# arduino.net
KiCad netlist of a schematic drawn in EAGLE
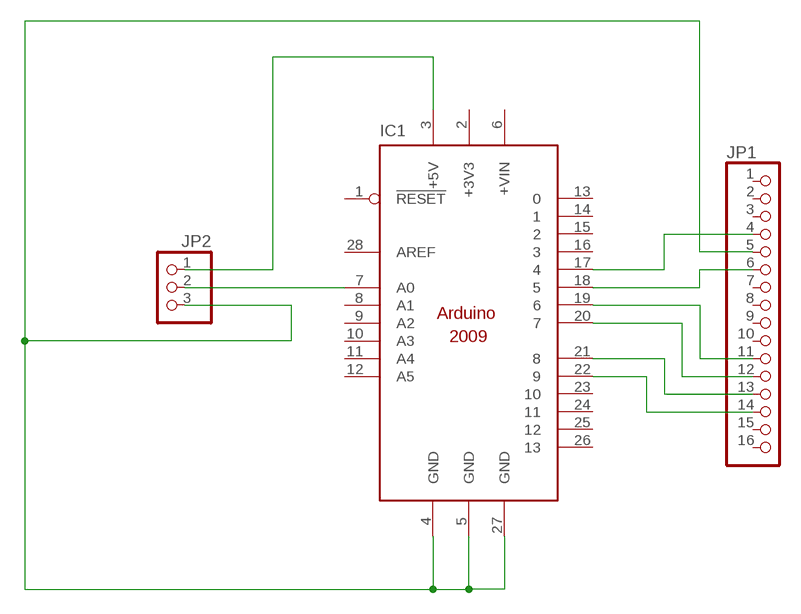
[diagram p0: schematic, sheet 1]

(export (version "E")
  (design (tool "Eeschema 10.0.6"))
  (components
    (comp (ref "IC1")
      (value "ARDUINO2009_12")
      (footprint "eagle-import:ARDUINO2009_2")
      (libsource (lib "eagle-import") (part "ARDUINO2009_12"))
    )
    (comp (ref "JP1")
      (value "PINHD-1X16")
      (footprint "eagle-import:1X16")
      (libsource (lib "eagle-import") (part "PINHD-1X16"))
    )
    (comp (ref "JP2")
      (value "PINHD-1X3")
      (footprint "eagle-import:1X03")
      (libsource (lib "eagle-import") (part "PINHD-1X3"))
    )
  )
  (nets
    (net (code "1") (name "/+3V3") (class "Default")
      (node (ref "IC1") (pin "2") (pinfunction "+3V3_2") (pintype "power_in"))
    )
    (net (code "2") (name "Net-(IC1-+5V)") (class "Default")
      (node (ref "IC1") (pin "3") (pinfunction "+5V_3") (pintype "power_in"))
      (node (ref "JP2") (pin "1") (pinfunction "1_1") (pintype "passive"))
    )
    (net (code "3") (name "Net-(IC1-4)") (class "Default")
      (node (ref "IC1") (pin "17") (pinfunction "4_17") (pintype "bidirectional"))
      (node (ref "JP1") (pin "4") (pinfunction "4_4") (pintype "passive"))
    )
    (net (code "4") (name "Net-(IC1-5)") (class "Default")
      (node (ref "IC1") (pin "18") (pinfunction "5_18") (pintype "bidirectional"))
      (node (ref "JP1") (pin "6") (pinfunction "6_6") (pintype "passive"))
    )
    (net (code "5") (name "Net-(IC1-6)") (class "Default")
      (node (ref "IC1") (pin "19") (pinfunction "6_19") (pintype "bidirectional"))
      (node (ref "JP1") (pin "11") (pinfunction "11_11") (pintype "passive"))
    )
    (net (code "6") (name "Net-(IC1-7)") (class "Default")
      (node (ref "IC1") (pin "20") (pinfunction "7_20") (pintype "bidirectional"))
      (node (ref "JP1") (pin "12") (pinfunction "12_12") (pintype "passive"))
    )
    (net (code "7") (name "Net-(IC1-8)") (class "Default")
      (node (ref "IC1") (pin "21") (pinfunction "8_21") (pintype "bidirectional"))
      (node (ref "JP1") (pin "13") (pinfunction "13_13") (pintype "passive"))
    )
    (net (code "8") (name "Net-(IC1-9)") (class "Default")
      (node (ref "IC1") (pin "22") (pinfunction "9_22") (pintype "bidirectional"))
      (node (ref "JP1") (pin "14") (pinfunction "14_14") (pintype "passive"))
    )
    (net (code "9") (name "Net-(IC1-A0)") (class "Default")
      (node (ref "IC1") (pin "7") (pinfunction "A0_7") (pintype "bidirectional"))
      (node (ref "JP2") (pin "2") (pinfunction "2_2") (pintype "passive"))
    )
    (net (code "10") (name "Net-(IC1-GND-Pad27)") (class "Default")
      (node (ref "IC1") (pin "27") (pinfunction "GND_27") (pintype "power_in"))
      (node (ref "IC1") (pin "4") (pinfunction "GND_4") (pintype "power_in"))
      (node (ref "IC1") (pin "5") (pinfunction "GND_5") (pintype "power_in"))
      (node (ref "JP1") (pin "5") (pinfunction "5_5") (pintype "passive"))
      (node (ref "JP2") (pin "3") (pinfunction "3_3") (pintype "passive"))
    )
    (net (code "11") (name "unconnected-(IC1-+VIN-Pad6)") (class "Default")
      (node (ref "IC1") (pin "6") (pinfunction "+VIN_6") (pintype "bidirectional"))
    )
    (net (code "12") (name "unconnected-(IC1-0-Pad13)") (class "Default")
      (node (ref "IC1") (pin "13") (pinfunction "0_13") (pintype "bidirectional"))
    )
    (net (code "13") (name "unconnected-(IC1-1-Pad14)") (class "Default")
      (node (ref "IC1") (pin "14") (pinfunction "1_14") (pintype "bidirectional"))
    )
    (net (code "14") (name "unconnected-(IC1-2-Pad15)") (class "Default")
      (node (ref "IC1") (pin "15") (pinfunction "2_15") (pintype "bidirectional"))
    )
    (net (code "15") (name "unconnected-(IC1-3-Pad16)") (class "Default")
      (node (ref "IC1") (pin "16") (pinfunction "3_16") (pintype "bidirectional"))
    )
    (net (code "16") (name "unconnected-(IC1-10-Pad23)") (class "Default")
      (node (ref "IC1") (pin "23") (pinfunction "10_23") (pintype "bidirectional"))
    )
    (net (code "17") (name "unconnected-(IC1-11-Pad24)") (class "Default")
      (node (ref "IC1") (pin "24") (pinfunction "11_24") (pintype "bidirectional"))
    )
    (net (code "18") (name "unconnected-(IC1-12-Pad25)") (class "Default")
      (node (ref "IC1") (pin "25") (pinfunction "12_25") (pintype "bidirectional"))
    )
    (net (code "19") (name "unconnected-(IC1-13-Pad26)") (class "Default")
      (node (ref "IC1") (pin "26") (pinfunction "13_26") (pintype "bidirectional"))
    )
    (net (code "20") (name "unconnected-(IC1-A1-Pad8)") (class "Default")
      (node (ref "IC1") (pin "8") (pinfunction "A1_8") (pintype "bidirectional"))
    )
    (net (code "21") (name "unconnected-(IC1-A2-Pad9)") (class "Default")
      (node (ref "IC1") (pin "9") (pinfunction "A2_9") (pintype "bidirectional"))
    )
    (net (code "22") (name "unconnected-(IC1-A3-Pad10)") (class "Default")
      (node (ref "IC1") (pin "10") (pinfunction "A3_10") (pintype "bidirectional"))
    )
    (net (code "23") (name "unconnected-(IC1-A4-Pad11)") (class "Default")
      (node (ref "IC1") (pin "11") (pinfunction "A4_11") (pintype "bidirectional"))
    )
    (net (code "24") (name "unconnected-(IC1-A5-Pad12)") (class "Default")
      (node (ref "IC1") (pin "12") (pinfunction "A5_12") (pintype "bidirectional"))
    )
    (net (code "25") (name "unconnected-(IC1-AREF-Pad28)") (class "Default")
      (node (ref "IC1") (pin "28") (pinfunction "AREF_28") (pintype "bidirectional"))
    )
    (net (code "26") (name "unconnected-(IC1-~{RESET}-Pad1)") (class "Default")
      (node (ref "IC1") (pin "1") (pinfunction "~{RESET}_1") (pintype "bidirectional"))
    )
    (net (code "27") (name "unconnected-(JP1-Pad1)") (class "Default")
      (node (ref "JP1") (pin "1") (pinfunction "1_1") (pintype "passive"))
    )
    (net (code "28") (name "unconnected-(JP1-Pad2)") (class "Default")
      (node (ref "JP1") (pin "2") (pinfunction "2_2") (pintype "passive"))
    )
    (net (code "29") (name "unconnected-(JP1-Pad3)") (class "Default")
      (node (ref "JP1") (pin "3") (pinfunction "3_3") (pintype "passive"))
    )
    (net (code "30") (name "unconnected-(JP1-Pad7)") (class "Default")
      (node (ref "JP1") (pin "7") (pinfunction "7_7") (pintype "passive"))
    )
    (net (code "31") (name "unconnected-(JP1-Pad8)") (class "Default")
      (node (ref "JP1") (pin "8") (pinfunction "8_8") (pintype "passive"))
    )
    (net (code "32") (name "unconnected-(JP1-Pad9)") (class "Default")
      (node (ref "JP1") (pin "9") (pinfunction "9_9") (pintype "passive"))
    )
    (net (code "33") (name "unconnected-(JP1-Pad10)") (class "Default")
      (node (ref "JP1") (pin "10") (pinfunction "10_10") (pintype "passive"))
    )
    (net (code "34") (name "unconnected-(JP1-Pad15)") (class "Default")
      (node (ref "JP1") (pin "15") (pinfunction "15_15") (pintype "passive"))
    )
    (net (code "35") (name "unconnected-(JP1-Pad16)") (class "Default")
      (node (ref "JP1") (pin "16") (pinfunction "16_16") (pintype "passive"))
    )
  )
)
